# AUDIO.net
KiCad netlist of a schematic drawn in Altium Designer
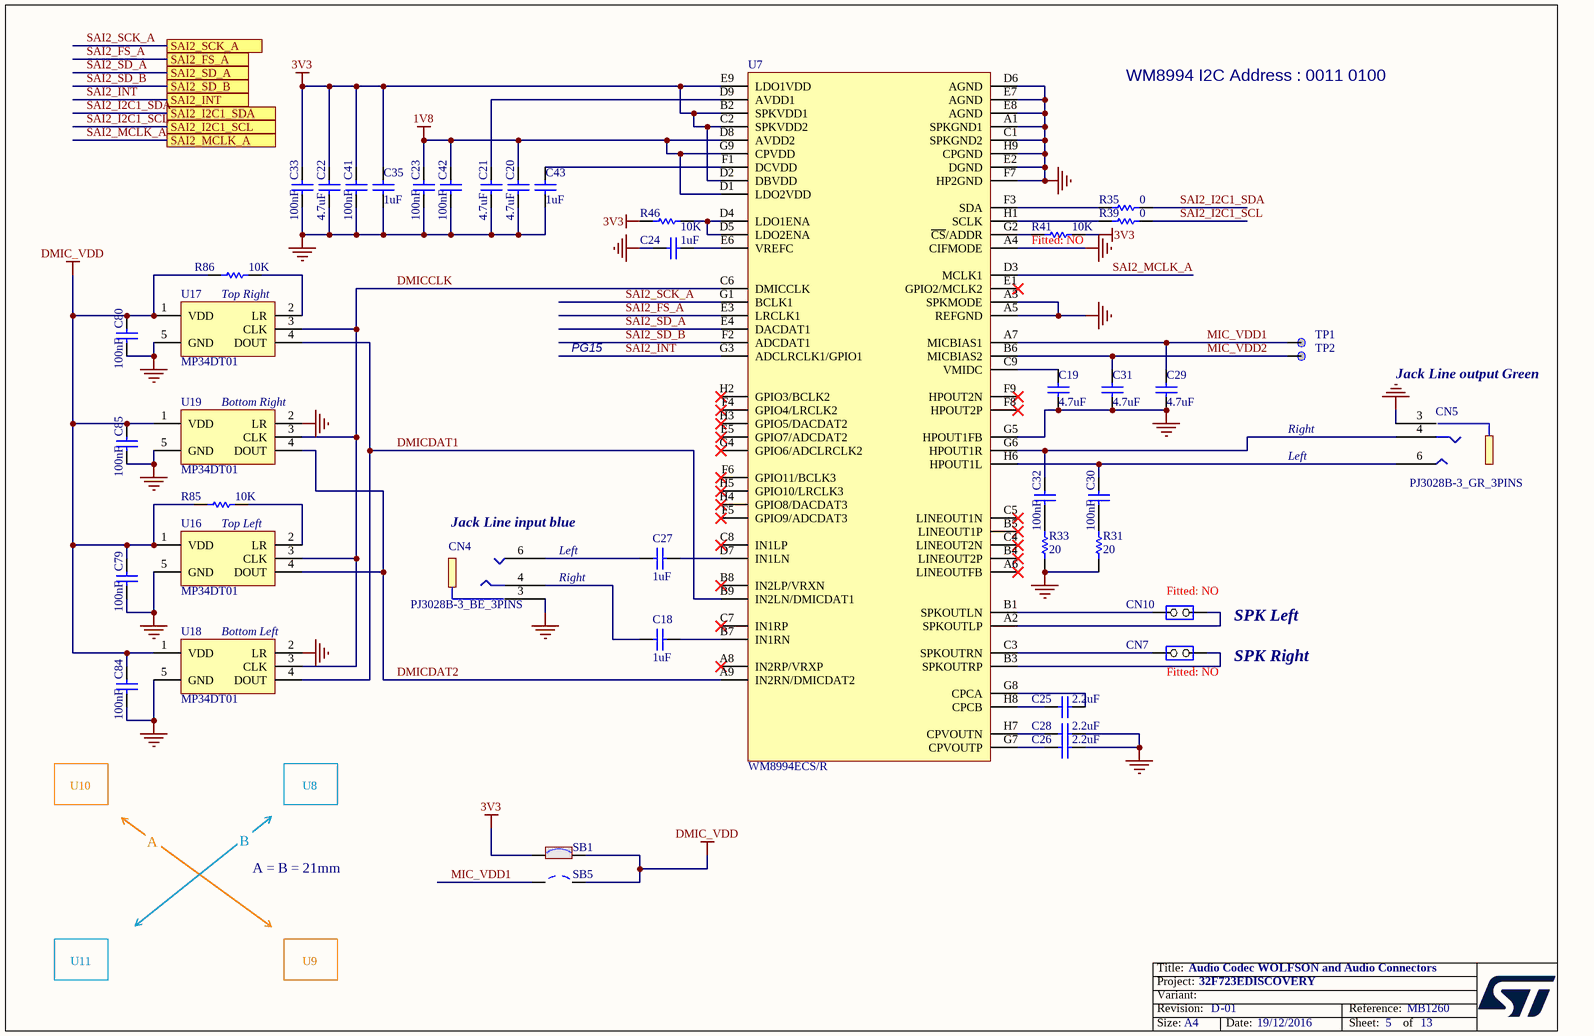
[diagram p0: AUDIO.SchDoc]

(export (version "E")
  (design (tool "Eeschema 10.0.6"))
  (components
    (comp (ref "C18")
      (value "1uF")
      (footprint "0603C")
      (description "Capacitor,1uF,16V,X5R,10%,0603,YAGEO")
      (libsource (lib "MCD_TOOLS_CAPACITOR") (part "Cap_1uF_X5R_10%_0603"))
    )
    (comp (ref "C19")
      (value "4.7uF")
      (footprint "0603C")
      (description "Capacitor,4.7uF,16V, X5R,10%,0603,YAGEO")
      (libsource (lib "MCD_TOOLS") (part "Cap_4.7uF_X5R_10%_0603"))
    )
    (comp (ref "C20")
      (value "4.7uF")
      (footprint "0603C")
      (description "Capacitor,4.7uF,16V, X5R,10%,0603,YAGEO")
      (libsource (lib "MCD_TOOLS") (part "Cap_4.7uF_X5R_10%_0603"))
    )
    (comp (ref "C21")
      (value "4.7uF")
      (footprint "0603C")
      (description "Capacitor,4.7uF,16V, X5R,10%,0603,YAGEO")
      (libsource (lib "MCD_TOOLS") (part "Cap_4.7uF_X5R_10%_0603"))
    )
    (comp (ref "C22")
      (value "4.7uF")
      (footprint "0603C")
      (description "Capacitor,4.7uF,16V, X5R,10%,0603,YAGEO")
      (libsource (lib "MCD_TOOLS") (part "Cap_4.7uF_X5R_10%_0603"))
    )
    (comp (ref "C23")
      (value "100nF")
      (footprint "0402C")
      (description "Capacitor,100nF,16V,X7R,10%,0402,YAGEO")
      (libsource (lib "MCD_TOOLS") (part "Cap_100nF_X7R_10%_0402"))
    )
    (comp (ref "C24")
      (value "1uF")
      (footprint "0603C")
      (description "Capacitor,1uF,16V,X5R,10%,0603,YAGEO")
      (libsource (lib "MCD_TOOLS_CAPACITOR") (part "Cap_1uF_X5R_10%_0603"))
    )
    (comp (ref "C25")
      (value "2.2uF")
      (footprint "0603C")
      (description "Capacitor,2.2uF,10V, X5R,10%,0603,YAGEO")
      (fields (field (name "Comment") "2.2uF_X5R_10%_0603"))
      (libsource (lib "MCD_TOOLS_CAPACITOR") (part "Cap_2.2uF_X5R_10%_0603"))
    )
    (comp (ref "C26")
      (value "2.2uF")
      (footprint "0603C")
      (description "Capacitor,2.2uF,10V, X5R,10%,0603,YAGEO")
      (fields (field (name "Comment") "2.2uF_X5R_10%_0603"))
      (libsource (lib "MCD_TOOLS_CAPACITOR") (part "Cap_2.2uF_X5R_10%_0603"))
    )
    (comp (ref "C27")
      (value "1uF")
      (footprint "0603C")
      (description "Capacitor,1uF,16V,X5R,10%,0603,YAGEO")
      (libsource (lib "MCD_TOOLS_CAPACITOR") (part "Cap_1uF_X5R_10%_0603"))
    )
    (comp (ref "C28")
      (value "2.2uF")
      (footprint "0603C")
      (description "Capacitor,2.2uF,10V, X5R,10%,0603,YAGEO")
      (fields (field (name "Comment") "2.2uF_X5R_10%_0603"))
      (libsource (lib "MCD_TOOLS_CAPACITOR") (part "Cap_2.2uF_X5R_10%_0603"))
    )
    (comp (ref "C29")
      (value "4.7uF")
      (footprint "0603C")
      (description "Capacitor,4.7uF,16V, X5R,10%,0603,YAGEO")
      (libsource (lib "MCD_TOOLS") (part "Cap_4.7uF_X5R_10%_0603"))
    )
    (comp (ref "C30")
      (value "100nF")
      (footprint "0402C")
      (description "Capacitor,100nF,16V,X7R,10%,0402,YAGEO")
      (libsource (lib "MCD_TOOLS") (part "Cap_100nF_X7R_10%_0402"))
    )
    (comp (ref "C31")
      (value "4.7uF")
      (footprint "0603C")
      (description "Capacitor,4.7uF,16V, X5R,10%,0603,YAGEO")
      (libsource (lib "MCD_TOOLS") (part "Cap_4.7uF_X5R_10%_0603"))
    )
    (comp (ref "C32")
      (value "100nF")
      (footprint "0402C")
      (description "Capacitor,100nF,16V,X7R,10%,0402,YAGEO")
      (libsource (lib "MCD_TOOLS") (part "Cap_100nF_X7R_10%_0402"))
    )
    (comp (ref "C33")
      (value "100nF")
      (footprint "0402C")
      (description "Capacitor,100nF,16V,X7R,10%,0402,YAGEO")
      (libsource (lib "MCD_TOOLS") (part "Cap_100nF_X7R_10%_0402"))
    )
    (comp (ref "C35")
      (value "1uF")
      (footprint "0603C")
      (description "Capacitor,1uF,16V,X5R,10%,0603,YAGEO")
      (libsource (lib "MCD_TOOLS_CAPACITOR") (part "Cap_1uF_X5R_10%_0603"))
    )
    (comp (ref "C41")
      (value "100nF")
      (footprint "0402C")
      (description "Capacitor,100nF,16V,X7R,10%,0402,YAGEO")
      (libsource (lib "MCD_TOOLS") (part "Cap_100nF_X7R_10%_0402"))
    )
    (comp (ref "C42")
      (value "100nF")
      (footprint "0402C")
      (description "Capacitor,100nF,16V,X7R,10%,0402,YAGEO")
      (libsource (lib "MCD_TOOLS") (part "Cap_100nF_X7R_10%_0402"))
    )
    (comp (ref "C43")
      (value "1uF")
      (footprint "0603C")
      (description "Capacitor,1uF,16V,X5R,10%,0603,YAGEO")
      (libsource (lib "MCD_TOOLS_CAPACITOR") (part "Cap_1uF_X5R_10%_0603"))
    )
    (comp (ref "C79")
      (value "100nF")
      (footprint "0402C")
      (description "Capacitor,100nF,16V,X7R,10%,0402,YAGEO")
      (libsource (lib "MCD_TOOLS") (part "Cap_100nF_X7R_10%_0402"))
    )
    (comp (ref "C80")
      (value "100nF")
      (footprint "0402C")
      (description "Capacitor,100nF,16V,X7R,10%,0402,YAGEO")
      (libsource (lib "MCD_TOOLS") (part "Cap_100nF_X7R_10%_0402"))
    )
    (comp (ref "C84")
      (value "100nF")
      (footprint "0402C")
      (description "Capacitor,100nF,16V,X7R,10%,0402,YAGEO")
      (libsource (lib "MCD_TOOLS") (part "Cap_100nF_X7R_10%_0402"))
    )
    (comp (ref "C85")
      (value "100nF")
      (footprint "0402C")
      (description "Capacitor,100nF,16V,X7R,10%,0402,YAGEO")
      (libsource (lib "MCD_TOOLS") (part "Cap_100nF_X7R_10%_0402"))
    )
    (comp (ref "CN4")
      (value "PJ3028B-3_BE_3PINS")
      (footprint "PJ3028B")
      (description "Connector Jack Stereo 3.5mm, female SMT, Blue (Line input)")
      (libsource (lib "MCD_TEMP_NPA") (part "PJ3028B-3_BE_3PINS"))
    )
    (comp (ref "CN5")
      (value "PJ3028B-3_GR_3PINS")
      (footprint "PJ3028B")
      (description "Connector Jack Stereo 3.5mm, female SMT, Green (Line output)")
      (libsource (lib "MCD_TEMP_NPA") (part "PJ3028B-3_GR_3PINS"))
    )
    (comp (ref "CN7")
      (value "JP2")
      (footprint "SIP2")
      (fields (field (name "FITTED") "NO"))
      (libsource (lib "MCD_TOOLS_CONNECTOR") (part "JP2"))
    )
    (comp (ref "CN10")
      (value "JP2")
      (footprint "SIP2")
      (fields (field (name "FITTED") "NO"))
      (libsource (lib "MCD_TOOLS_CONNECTOR") (part "JP2"))
    )
    (comp (ref "R31")
      (value "20")
      (footprint "0402R")
      (description "Resistor,20,0402,1%,YAGEO")
      (libsource (lib "MCD_TOOLS") (part "Res_20_1%_0402"))
    )
    (comp (ref "R33")
      (value "20")
      (footprint "0402R")
      (description "Resistor,20,0402,1%,YAGEO")
      (libsource (lib "MCD_TOOLS") (part "Res_20_1%_0402"))
    )
    (comp (ref "R35")
      (value "0")
      (footprint "0402R")
      (description "Resistor,0,0402,5%,YAGEO")
      (libsource (lib "MCD_TOOLS") (part "Res_0_5%_0402"))
    )
    (comp (ref "R39")
      (value "0")
      (footprint "0402R")
      (description "Resistor,0,0402,5%,YAGEO")
      (libsource (lib "MCD_TOOLS") (part "Res_0_5%_0402"))
    )
    (comp (ref "R41")
      (value "10K")
      (footprint "0402R")
      (description "Resistor,10K,0402,1%,YAGEO")
      (fields (field (name "FITTED") "NO"))
      (libsource (lib "MCD_TOOLS") (part "Res_10K_1%_0402"))
    )
    (comp (ref "R46")
      (value "10K")
      (footprint "0402R")
      (description "Resistor,10K,0402,1%,YAGEO")
      (libsource (lib "MCD_TOOLS") (part "Res_10K_1%_0402"))
    )
    (comp (ref "R85")
      (value "10K")
      (footprint "0402R")
      (description "Resistor,10K,0402,1%,YAGEO")
      (libsource (lib "MCD_TOOLS") (part "Res_10K_1%_0402"))
    )
    (comp (ref "R86")
      (value "10K")
      (footprint "0402R")
      (description "Resistor,10K,0402,1%,YAGEO")
      (libsource (lib "MCD_TOOLS") (part "Res_10K_1%_0402"))
    )
    (comp (ref "SB1")
      (value "Solder Bridge ON")
      (footprint "JP2_SMD")
      (libsource (lib "MCD_TOOLS") (part "SB_ON"))
    )
    (comp (ref "SB5")
      (value "Solder Bridge OFF")
      (footprint "JP2_SMD")
      (libsource (lib "MCD_TOOLS") (part "SB_OFF"))
    )
    (comp (ref "TP1")
      (value "TP")
      (footprint "TP_C40")
      (description "Test Point")
      (libsource (lib "MCD_TOOLS_CONNECTOR") (part "TP"))
    )
    (comp (ref "TP2")
      (value "TP")
      (footprint "TP_C40")
      (description "Test Point")
      (libsource (lib "MCD_TOOLS_CONNECTOR") (part "TP"))
    )
    (comp (ref "U7")
      (value "WM8994ECS/R")
      (footprint "BGA72_0R5_4R5X4")
      (description "Multi-Channel Audio Hub CODEC for Smartphones")
      (libsource (lib "MCD_TOOLS") (part "WM8994ECS/R"))
    )
    (comp (ref "U16")
      (value "MP34DT01")
      (footprint "MP34DT01TR")
      (description "MEMS audio sensor, omnidirectional digital microphone")
      (libsource (lib "MCD_TOOLS_MISCELLANEOUS") (part "MP34DT01"))
    )
    (comp (ref "U17")
      (value "MP34DT01")
      (footprint "MP34DT01TR")
      (description "MEMS audio sensor, omnidirectional digital microphone")
      (libsource (lib "MCD_TOOLS_MISCELLANEOUS") (part "MP34DT01"))
    )
    (comp (ref "U18")
      (value "MP34DT01")
      (footprint "MP34DT01TR")
      (description "MEMS audio sensor, omnidirectional digital microphone")
      (libsource (lib "MCD_TOOLS_MISCELLANEOUS") (part "MP34DT01"))
    )
    (comp (ref "U19")
      (value "MP34DT01")
      (footprint "MP34DT01TR")
      (description "MEMS audio sensor, omnidirectional digital microphone")
      (libsource (lib "MCD_TOOLS_MISCELLANEOUS") (part "MP34DT01"))
    )
  )
  (nets
    (net (code "1") (name "/DMICCLK") (class "Default")
      (node (ref "U16") (pin "3") (pinfunction "CLK_3") (pintype "passive"))
      (node (ref "U17") (pin "3") (pinfunction "CLK_3") (pintype "passive"))
      (node (ref "U18") (pin "3") (pinfunction "CLK_3") (pintype "passive"))
      (node (ref "U19") (pin "3") (pinfunction "CLK_3") (pintype "passive"))
      (node (ref "U7") (pin "C6") (pinfunction "DMICCLK_C6") (pintype "passive"))
    )
    (net (code "2") (name "/DMICDAT1") (class "Default")
      (node (ref "U17") (pin "4") (pinfunction "DOUT_4") (pintype "passive"))
      (node (ref "U18") (pin "4") (pinfunction "DOUT_4") (pintype "passive"))
      (node (ref "U7") (pin "B9") (pinfunction "IN2LN/DMICDAT1_B9") (pintype "passive"))
    )
    (net (code "3") (name "/DMICDAT2") (class "Default")
      (node (ref "U16") (pin "4") (pinfunction "DOUT_4") (pintype "passive"))
      (node (ref "U19") (pin "4") (pinfunction "DOUT_4") (pintype "passive"))
      (node (ref "U7") (pin "A9") (pinfunction "IN2RN/DMICDAT2_A9") (pintype "passive"))
    )
    (net (code "4") (name "/MIC_VDD1") (class "Default")
      (node (ref "C29") (pin "2") (pinfunction "2_2") (pintype "passive"))
      (node (ref "SB5") (pin "1") (pinfunction "1_1") (pintype "passive"))
      (node (ref "TP1") (pin "1") (pinfunction "1_1") (pintype "passive"))
      (node (ref "U7") (pin "A7") (pinfunction "MICBIAS1_A7") (pintype "passive"))
    )
    (net (code "5") (name "/MIC_VDD2") (class "Default")
      (node (ref "C31") (pin "2") (pinfunction "2_2") (pintype "passive"))
      (node (ref "TP2") (pin "1") (pinfunction "1_1") (pintype "passive"))
      (node (ref "U7") (pin "B6") (pinfunction "MICBIAS2_B6") (pintype "passive"))
    )
    (net (code "6") (name "/SAI2_FS_A") (class "Default")
      (node (ref "U7") (pin "E3") (pinfunction "LRCLK1_E3") (pintype "passive"))
    )
    (net (code "7") (name "/SAI2_I2C1_SCL") (class "Default")
      (node (ref "R39") (pin "1") (pinfunction "1_1") (pintype "passive"))
    )
    (net (code "8") (name "/SAI2_I2C1_SDA") (class "Default")
      (node (ref "R35") (pin "1") (pinfunction "1_1") (pintype "passive"))
    )
    (net (code "9") (name "/SAI2_INT") (class "Default")
      (node (ref "U7") (pin "G3") (pinfunction "ADCLRCLK1/GPIO1_G3") (pintype "passive"))
    )
    (net (code "10") (name "/SAI2_MCLK_A") (class "Default")
      (node (ref "U7") (pin "D3") (pinfunction "MCLK1_D3") (pintype "passive"))
    )
    (net (code "11") (name "/SAI2_SCK_A") (class "Default")
      (node (ref "U7") (pin "G1") (pinfunction "BCLK1_G1") (pintype "passive"))
    )
    (net (code "12") (name "/SAI2_SD_A") (class "Default")
      (node (ref "U7") (pin "E4") (pinfunction "DACDAT1_E4") (pintype "passive"))
    )
    (net (code "13") (name "/SAI2_SD_B") (class "Default")
      (node (ref "U7") (pin "F2") (pinfunction "ADCDAT1_F2") (pintype "passive"))
    )
    (net (code "14") (name "1V8") (class "Default")
      (node (ref "C20") (pin "1") (pinfunction "1_1") (pintype "passive"))
      (node (ref "C23") (pin "1") (pinfunction "1_1") (pintype "passive"))
      (node (ref "C42") (pin "1") (pinfunction "1_1") (pintype "passive"))
      (node (ref "U7") (pin "D1") (pinfunction "LDO2VDD_D1") (pintype "passive"))
      (node (ref "U7") (pin "D8") (pinfunction "AVDD2_D8") (pintype "passive"))
      (node (ref "U7") (pin "G9") (pinfunction "CPVDD_G9") (pintype "passive"))
    )
    (net (code "15") (name "3V3") (class "Default")
      (node (ref "C22") (pin "1") (pinfunction "1_1") (pintype "passive"))
      (node (ref "C33") (pin "1") (pinfunction "1_1") (pintype "passive"))
      (node (ref "C35") (pin "2") (pinfunction "2_2") (pintype "passive"))
      (node (ref "C41") (pin "1") (pinfunction "1_1") (pintype "passive"))
      (node (ref "R41") (pin "1") (pinfunction "1_1") (pintype "passive"))
      (node (ref "R46") (pin "2") (pinfunction "2_2") (pintype "passive"))
      (node (ref "SB1") (pin "1") (pinfunction "1_1") (pintype "passive"))
      (node (ref "U7") (pin "B2") (pinfunction "SPKVDD1_B2") (pintype "passive"))
      (node (ref "U7") (pin "C2") (pinfunction "SPKVDD2_C2") (pintype "passive"))
      (node (ref "U7") (pin "D2") (pinfunction "DBVDD_D2") (pintype "passive"))
      (node (ref "U7") (pin "E9") (pinfunction "LDO1VDD_E9") (pintype "passive"))
    )
    (net (code "16") (name "DMIC_VDD") (class "Default")
      (node (ref "C79") (pin "1") (pinfunction "1_1") (pintype "passive"))
      (node (ref "C80") (pin "1") (pinfunction "1_1") (pintype "passive"))
      (node (ref "C84") (pin "1") (pinfunction "1_1") (pintype "passive"))
      (node (ref "C85") (pin "1") (pinfunction "1_1") (pintype "passive"))
      (node (ref "R85") (pin "2") (pinfunction "2_2") (pintype "passive"))
      (node (ref "R86") (pin "2") (pinfunction "2_2") (pintype "passive"))
      (node (ref "SB1") (pin "2") (pinfunction "2_2") (pintype "passive"))
      (node (ref "SB5") (pin "2") (pinfunction "2_2") (pintype "passive"))
      (node (ref "U16") (pin "1") (pinfunction "VDD_1") (pintype "passive"))
      (node (ref "U17") (pin "1") (pinfunction "VDD_1") (pintype "passive"))
      (node (ref "U18") (pin "1") (pinfunction "VDD_1") (pintype "passive"))
      (node (ref "U19") (pin "1") (pinfunction "VDD_1") (pintype "passive"))
    )
    (net (code "17") (name "GND") (class "Default")
      (node (ref "C19") (pin "1") (pinfunction "1_1") (pintype "passive"))
      (node (ref "C20") (pin "2") (pinfunction "2_2") (pintype "passive"))
      (node (ref "C21") (pin "2") (pinfunction "2_2") (pintype "passive"))
      (node (ref "C22") (pin "2") (pinfunction "2_2") (pintype "passive"))
      (node (ref "C23") (pin "2") (pinfunction "2_2") (pintype "passive"))
      (node (ref "C24") (pin "2") (pinfunction "2_2") (pintype "passive"))
      (node (ref "C26") (pin "2") (pinfunction "2_2") (pintype "passive"))
      (node (ref "C28") (pin "2") (pinfunction "2_2") (pintype "passive"))
      (node (ref "C29") (pin "1") (pinfunction "1_1") (pintype "passive"))
      (node (ref "C31") (pin "1") (pinfunction "1_1") (pintype "passive"))
      (node (ref "C33") (pin "2") (pinfunction "2_2") (pintype "passive"))
      (node (ref "C35") (pin "1") (pinfunction "1_1") (pintype "passive"))
      (node (ref "C41") (pin "2") (pinfunction "2_2") (pintype "passive"))
      (node (ref "C42") (pin "2") (pinfunction "2_2") (pintype "passive"))
      (node (ref "C43") (pin "1") (pinfunction "1_1") (pintype "passive"))
      (node (ref "C79") (pin "2") (pinfunction "2_2") (pintype "passive"))
      (node (ref "C80") (pin "2") (pinfunction "2_2") (pintype "passive"))
      (node (ref "C84") (pin "2") (pinfunction "2_2") (pintype "passive"))
      (node (ref "C85") (pin "2") (pinfunction "2_2") (pintype "passive"))
      (node (ref "CN4") (pin "3") (pintype "passive"))
      (node (ref "CN5") (pin "3") (pintype "passive"))
      (node (ref "R31") (pin "2") (pinfunction "2_2") (pintype "passive"))
      (node (ref "R33") (pin "2") (pinfunction "2_2") (pintype "passive"))
      (node (ref "U16") (pin "5") (pinfunction "GND_5") (pintype "passive"))
      (node (ref "U17") (pin "5") (pinfunction "GND_5") (pintype "passive"))
      (node (ref "U18") (pin "2") (pinfunction "LR_2") (pintype "passive"))
      (node (ref "U18") (pin "5") (pinfunction "GND_5") (pintype "passive"))
      (node (ref "U19") (pin "2") (pinfunction "LR_2") (pintype "passive"))
      (node (ref "U19") (pin "5") (pinfunction "GND_5") (pintype "passive"))
      (node (ref "U7") (pin "A1") (pinfunction "SPKGND1_A1") (pintype "passive"))
      (node (ref "U7") (pin "A3") (pinfunction "SPKMODE_A3") (pintype "passive"))
      (node (ref "U7") (pin "A4") (pinfunction "CIFMODE_A4") (pintype "passive"))
      (node (ref "U7") (pin "A5") (pinfunction "REFGND_A5") (pintype "passive"))
      (node (ref "U7") (pin "C1") (pinfunction "SPKGND2_C1") (pintype "passive"))
      (node (ref "U7") (pin "D6") (pinfunction "AGND_D6") (pintype "passive"))
      (node (ref "U7") (pin "E2") (pinfunction "DGND_E2") (pintype "passive"))
      (node (ref "U7") (pin "E7") (pinfunction "AGND_E7") (pintype "passive"))
      (node (ref "U7") (pin "E8") (pinfunction "AGND_E8") (pintype "passive"))
      (node (ref "U7") (pin "F7") (pinfunction "HP2GND_F7") (pintype "passive"))
      (node (ref "U7") (pin "G5") (pinfunction "HPOUT1FB_G5") (pintype "passive"))
      (node (ref "U7") (pin "H9") (pinfunction "CPGND_H9") (pintype "passive"))
    )
    (net (code "18") (name "Net-(C18-Pad2)") (class "Default")
      (node (ref "C18") (pin "2") (pinfunction "2_2") (pintype "passive"))
      (node (ref "CN4") (pin "4") (pintype "passive"))
    )
    (net (code "19") (name "Net-(C27-Pad2)") (class "Default")
      (node (ref "C27") (pin "2") (pinfunction "2_2") (pintype "passive"))
      (node (ref "CN4") (pin "6") (pintype "passive"))
    )
    (net (code "20") (name "Net-(C30-Pad2)") (class "Default")
      (node (ref "C30") (pin "2") (pinfunction "2_2") (pintype "passive"))
      (node (ref "R31") (pin "1") (pinfunction "1_1") (pintype "passive"))
    )
    (net (code "21") (name "Net-(C32-Pad2)") (class "Default")
      (node (ref "C32") (pin "2") (pinfunction "2_2") (pintype "passive"))
      (node (ref "R33") (pin "1") (pinfunction "1_1") (pintype "passive"))
    )
    (net (code "22") (name "Net-(CN7-COMMON)") (class "Default")
      (node (ref "CN7") (pin "1") (pinfunction "COMMON_1") (pintype "passive"))
      (node (ref "U7") (pin "C3") (pinfunction "SPKOUTRN_C3") (pintype "passive"))
    )
    (net (code "23") (name "Net-(CN7-NO)") (class "Default")
      (node (ref "CN7") (pin "2") (pinfunction "NO_2") (pintype "passive"))
      (node (ref "U7") (pin "B3") (pinfunction "SPKOUTRP_B3") (pintype "passive"))
    )
    (net (code "24") (name "Net-(CN10-COMMON)") (class "Default")
      (node (ref "CN10") (pin "1") (pinfunction "COMMON_1") (pintype "passive"))
      (node (ref "U7") (pin "B1") (pinfunction "SPKOUTLN_B1") (pintype "passive"))
    )
    (net (code "25") (name "Net-(CN10-NO)") (class "Default")
      (node (ref "CN10") (pin "2") (pinfunction "NO_2") (pintype "passive"))
      (node (ref "U7") (pin "A2") (pinfunction "SPKOUTLP_A2") (pintype "passive"))
    )
    (net (code "26") (name "Net-(U7-AVDD1)") (class "Default")
      (node (ref "C21") (pin "1") (pinfunction "1_1") (pintype "passive"))
      (node (ref "U7") (pin "D9") (pinfunction "AVDD1_D9") (pintype "passive"))
    )
    (net (code "27") (name "Net-(U7-CPCA)") (class "Default")
      (node (ref "C25") (pin "2") (pinfunction "2_2") (pintype "passive"))
      (node (ref "U7") (pin "G8") (pinfunction "CPCA_G8") (pintype "passive"))
    )
    (net (code "28") (name "Net-(U7-CPCB)") (class "Default")
      (node (ref "C25") (pin "1") (pinfunction "1_1") (pintype "passive"))
      (node (ref "U7") (pin "H8") (pinfunction "CPCB_H8") (pintype "passive"))
    )
    (net (code "29") (name "Net-(U7-CPVOUTN)") (class "Default")
      (node (ref "C28") (pin "1") (pinfunction "1_1") (pintype "passive"))
      (node (ref "U7") (pin "H7") (pinfunction "CPVOUTN_H7") (pintype "passive"))
    )
    (net (code "30") (name "Net-(U7-CPVOUTP)") (class "Default")
      (node (ref "C26") (pin "1") (pinfunction "1_1") (pintype "passive"))
      (node (ref "U7") (pin "G7") (pinfunction "CPVOUTP_G7") (pintype "passive"))
    )
    (net (code "31") (name "Net-(U7-DCVDD)") (class "Default")
      (node (ref "C43") (pin "2") (pinfunction "2_2") (pintype "passive"))
      (node (ref "U7") (pin "F1") (pinfunction "DCVDD_F1") (pintype "passive"))
    )
    (net (code "32") (name "Net-(U7-HPOUT1L)") (class "Default")
      (node (ref "C30") (pin "1") (pinfunction "1_1") (pintype "passive"))
      (node (ref "CN5") (pin "6") (pintype "passive"))
      (node (ref "U7") (pin "H6") (pinfunction "HPOUT1L_H6") (pintype "passive"))
    )
    (net (code "33") (name "Net-(U7-HPOUT1R)") (class "Default")
      (node (ref "C32") (pin "1") (pinfunction "1_1") (pintype "passive"))
      (node (ref "CN5") (pin "4") (pintype "passive"))
      (node (ref "U7") (pin "G6") (pinfunction "HPOUT1R_G6") (pintype "passive"))
    )
    (net (code "34") (name "Net-(U7-IN1LN)") (class "Default")
      (node (ref "C27") (pin "1") (pinfunction "1_1") (pintype "passive"))
      (node (ref "U7") (pin "D7") (pinfunction "IN1LN_D7") (pintype "passive"))
    )
    (net (code "35") (name "Net-(U7-IN1RN)") (class "Default")
      (node (ref "C18") (pin "1") (pinfunction "1_1") (pintype "passive"))
      (node (ref "U7") (pin "B7") (pinfunction "IN1RN_B7") (pintype "passive"))
    )
    (net (code "36") (name "Net-(U7-LDO1ENA)") (class "Default")
      (node (ref "R46") (pin "1") (pinfunction "1_1") (pintype "passive"))
      (node (ref "U7") (pin "D4") (pinfunction "LDO1ENA_D4") (pintype "passive"))
      (node (ref "U7") (pin "D5") (pinfunction "LDO2ENA_D5") (pintype "passive"))
    )
    (net (code "37") (name "Net-(U7-SCLK)") (class "Default")
      (node (ref "R39") (pin "2") (pinfunction "2_2") (pintype "passive"))
      (node (ref "U7") (pin "H1") (pinfunction "SCLK_H1") (pintype "passive"))
    )
    (net (code "38") (name "Net-(U7-SDA)") (class "Default")
      (node (ref "R35") (pin "2") (pinfunction "2_2") (pintype "passive"))
      (node (ref "U7") (pin "F3") (pinfunction "SDA_F3") (pintype "passive"))
    )
    (net (code "39") (name "Net-(U7-VMIDC)") (class "Default")
      (node (ref "C19") (pin "2") (pinfunction "2_2") (pintype "passive"))
      (node (ref "U7") (pin "C9") (pinfunction "VMIDC_C9") (pintype "passive"))
    )
    (net (code "40") (name "Net-(U7-VREFC)") (class "Default")
      (node (ref "C24") (pin "1") (pinfunction "1_1") (pintype "passive"))
      (node (ref "U7") (pin "E6") (pinfunction "VREFC_E6") (pintype "passive"))
    )
    (net (code "41") (name "Net-(U7-~{CS}{slash}ADDR)") (class "Default")
      (node (ref "R41") (pin "2") (pinfunction "2_2") (pintype "passive"))
      (node (ref "U7") (pin "G2") (pinfunction "~{CS}/ADDR_G2") (pintype "passive"))
    )
    (net (code "42") (name "Net-(U16-LR)") (class "Default")
      (node (ref "R85") (pin "1") (pinfunction "1_1") (pintype "passive"))
      (node (ref "U16") (pin "2") (pinfunction "LR_2") (pintype "passive"))
    )
    (net (code "43") (name "Net-(U17-LR)") (class "Default")
      (node (ref "R86") (pin "1") (pinfunction "1_1") (pintype "passive"))
      (node (ref "U17") (pin "2") (pinfunction "LR_2") (pintype "passive"))
    )
    (net (code "44") (name "unconnected-(U7-GPIO2{slash}MCLK2-PadE1)") (class "Default")
      (node (ref "U7") (pin "E1") (pinfunction "GPIO2/MCLK2_E1") (pintype "passive+no_connect"))
    )
    (net (code "45") (name "unconnected-(U7-GPIO3{slash}BCLK2-PadH2)") (class "Default")
      (node (ref "U7") (pin "H2") (pinfunction "GPIO3/BCLK2_H2") (pintype "passive+no_connect"))
    )
    (net (code "46") (name "unconnected-(U7-GPIO4{slash}LRCLK2-PadF4)") (class "Default")
      (node (ref "U7") (pin "F4") (pinfunction "GPIO4/LRCLK2_F4") (pintype "passive+no_connect"))
    )
    (net (code "47") (name "unconnected-(U7-GPIO5{slash}DACDAT2-PadH3)") (class "Default")
      (node (ref "U7") (pin "H3") (pinfunction "GPIO5/DACDAT2_H3") (pintype "passive+no_connect"))
    )
    (net (code "48") (name "unconnected-(U7-GPIO6{slash}ADCLRCLK2-PadG4)") (class "Default")
      (node (ref "U7") (pin "G4") (pinfunction "GPIO6/ADCLRCLK2_G4") (pintype "passive+no_connect"))
    )
    (net (code "49") (name "unconnected-(U7-GPIO7{slash}ADCDAT2-PadE5)") (class "Default")
      (node (ref "U7") (pin "E5") (pinfunction "GPIO7/ADCDAT2_E5") (pintype "passive+no_connect"))
    )
    (net (code "50") (name "unconnected-(U7-GPIO8{slash}DACDAT3-PadH4)") (class "Default")
      (node (ref "U7") (pin "H4") (pinfunction "GPIO8/DACDAT3_H4") (pintype "passive+no_connect"))
    )
    (net (code "51") (name "unconnected-(U7-GPIO9{slash}ADCDAT3-PadF5)") (class "Default")
      (node (ref "U7") (pin "F5") (pinfunction "GPIO9/ADCDAT3_F5") (pintype "passive+no_connect"))
    )
    (net (code "52") (name "unconnected-(U7-GPIO10{slash}LRCLK3-PadH5)") (class "Default")
      (node (ref "U7") (pin "H5") (pinfunction "GPIO10/LRCLK3_H5") (pintype "passive+no_connect"))
    )
    (net (code "53") (name "unconnected-(U7-GPIO11{slash}BCLK3-PadF6)") (class "Default")
      (node (ref "U7") (pin "F6") (pinfunction "GPIO11/BCLK3_F6") (pintype "passive+no_connect"))
    )
    (net (code "54") (name "unconnected-(U7-HPOUT2N-PadF9)") (class "Default")
      (node (ref "U7") (pin "F9") (pinfunction "HPOUT2N_F9") (pintype "passive+no_connect"))
    )
    (net (code "55") (name "unconnected-(U7-HPOUT2P-PadF8)") (class "Default")
      (node (ref "U7") (pin "F8") (pinfunction "HPOUT2P_F8") (pintype "passive+no_connect"))
    )
    (net (code "56") (name "unconnected-(U7-IN1LP-PadC8)") (class "Default")
      (node (ref "U7") (pin "C8") (pinfunction "IN1LP_C8") (pintype "passive+no_connect"))
    )
    (net (code "57") (name "unconnected-(U7-IN1RP-PadC7)") (class "Default")
      (node (ref "U7") (pin "C7") (pinfunction "IN1RP_C7") (pintype "passive+no_connect"))
    )
    (net (code "58") (name "unconnected-(U7-IN2LP{slash}VRXN-PadB8)") (class "Default")
      (node (ref "U7") (pin "B8") (pinfunction "IN2LP/VRXN_B8") (pintype "passive+no_connect"))
    )
    (net (code "59") (name "unconnected-(U7-IN2RP{slash}VRXP-PadA8)") (class "Default")
      (node (ref "U7") (pin "A8") (pinfunction "IN2RP/VRXP_A8") (pintype "passive+no_connect"))
    )
    (net (code "60") (name "unconnected-(U7-LINEOUT1N-PadC5)") (class "Default")
      (node (ref "U7") (pin "C5") (pinfunction "LINEOUT1N_C5") (pintype "passive+no_connect"))
    )
    (net (code "61") (name "unconnected-(U7-LINEOUT1P-PadB5)") (class "Default")
      (node (ref "U7") (pin "B5") (pinfunction "LINEOUT1P_B5") (pintype "passive+no_connect"))
    )
    (net (code "62") (name "unconnected-(U7-LINEOUT2N-PadC4)") (class "Default")
      (node (ref "U7") (pin "C4") (pinfunction "LINEOUT2N_C4") (pintype "passive+no_connect"))
    )
    (net (code "63") (name "unconnected-(U7-LINEOUT2P-PadB4)") (class "Default")
      (node (ref "U7") (pin "B4") (pinfunction "LINEOUT2P_B4") (pintype "passive+no_connect"))
    )
    (net (code "64") (name "unconnected-(U7-LINEOUTFB-PadA6)") (class "Default")
      (node (ref "U7") (pin "A6") (pinfunction "LINEOUTFB_A6") (pintype "passive+no_connect"))
    )
  )
)
